# Sheet3.net
KiCad netlist of a schematic drawn in Altium Designer
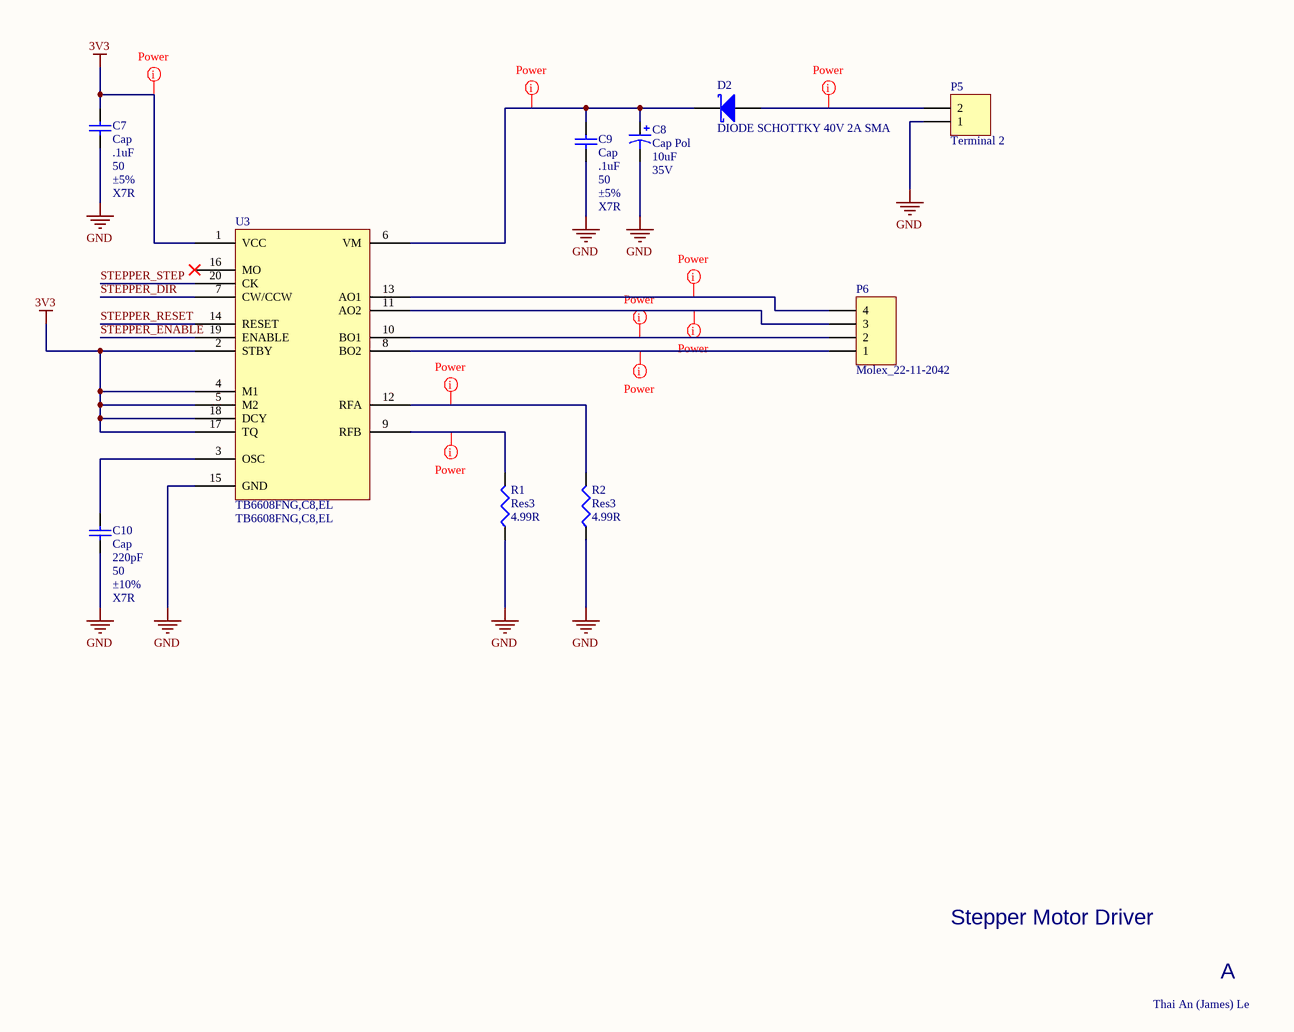
[diagram p0: Sheet3.SchDoc]

(export (version "E")
  (design (tool "Eeschema 10.0.6"))
  (components
    (comp (ref "C7")
      (value "Cap")
      (footprint "CAPC2012X09M")
      (description "CAP CER .1uF 50v X7R 0805")
      (fields
        (field (name "ALTIUM_VALUE") ".1uF")
        (field (name "WV") "50")
        (field (name "TOLERANCE") "±5%")
        (field (name "TYPE") "X7R")
        (field (name "MPN") "C0805C104J5RACTU")
      )
      (libsource (lib "esd_library") (part "CAP-X7R-.1uF-50V-±5%"))
    )
    (comp (ref "C8")
      (value "Cap Pol")
      (footprint "CAPACITOR_5MM")
      (description "CAP 85C 10uF ±20% 35V WX Series Aluminum Electrolytic")
      (fields
        (field (name "ALTIUM_VALUE") "10uF")
        (field (name "VOLTAGE") "35V")
        (field (name "MPN") "UWX1V100MCL1GB")
      )
      (libsource (lib "esd_library") (part "Cap Polar-10uF-35V"))
    )
    (comp (ref "C9")
      (value "Cap")
      (footprint "CAPC2012X09M")
      (description "CAP CER .1uF 50v X7R 0805")
      (fields
        (field (name "ALTIUM_VALUE") ".1uF")
        (field (name "WV") "50")
        (field (name "TOLERANCE") "±5%")
        (field (name "TYPE") "X7R")
        (field (name "MPN") "C0805C104J5RACTU")
      )
      (libsource (lib "esd_library") (part "CAP-X7R-.1uF-50V-±5%"))
    )
    (comp (ref "C10")
      (value "Cap")
      (footprint "CAPC2012X09M")
      (description "CAP CER 220pF 50v X7R 0805")
      (fields
        (field (name "ALTIUM_VALUE") "220pF")
        (field (name "WV") "50")
        (field (name "TOLERANCE") "±10%")
        (field (name "TYPE") "X7R")
        (field (name "MPN") "C0805C221K5RACTU")
      )
      (libsource (lib "esd_library") (part "CAP-X7R-220pF-50V-±10%"))
    )
    (comp (ref "D2")
      (value "DIODE SCHOTTKY 40V 2A SMA")
      (footprint "DIOM4326X23M")
      (description "Schottky Rectifier")
      (fields (field (name "MPN") "B240A-13-F"))
      (libsource (lib "esd_library") (part "DIODE SCHOTTKY 40V 2A SMA"))
    )
    (comp (ref "P5")
      (value "Terminal 2")
      (footprint "TYCO_282841_2")
      (description "Terminal, 2-Pin")
      (fields (field (name "MPN") "282841-2") (field (name "PUBLISHER") "Altium Limited"))
      (libsource (lib "esd_library") (part "Terminal 2"))
    )
    (comp (ref "P6")
      (value "Molex_22-11-2042")
      (footprint "MOLEX-22-11-2042")
      (description "CONN HEADER 4POS .100 VERT GOLD")
      (fields (field (name "MPN") "0022112042"))
      (libsource (lib "esd_library") (part "Molex_22-11-2042"))
    )
    (comp (ref "R1")
      (value "Res3")
      (footprint "RESC2112X05M")
      (description "RES SMD 4.99R OHM 1% 1/8W 0805")
      (fields (field (name "ALTIUM_VALUE") "4.99R") (field (name "MPN") "CRCW08054R99FKEA"))
      (libsource (lib "esd_library") (part "Resistor_4.99R"))
    )
    (comp (ref "R2")
      (value "Res3")
      (footprint "RESC2112X05M")
      (description "RES SMD 4.99R OHM 1% 1/8W 0805")
      (fields (field (name "ALTIUM_VALUE") "4.99R") (field (name "MPN") "CRCW08054R99FKEA"))
      (libsource (lib "esd_library") (part "Resistor_4.99R"))
    )
    (comp (ref "U3")
      (value "TB6608FNG,C8,EL")
      (footprint "TSOP65P640X160-20M")
      (description "IC MTR DRV BIPLR 2.7-5.5V 20SSOP")
      (fields (field (name "MPN") "TB6608FNG,C8,EL"))
      (libsource (lib "esd_library") (part "TB6608FNG,C8,EL"))
    )
  )
  (nets
    (net (code "1") (name "/STEPPER_DIR") (class "Default")
      (node (ref "U3") (pin "7") (pinfunction "CW/CCW_7") (pintype "passive"))
    )
    (net (code "2") (name "/STEPPER_ENABLE") (class "Default")
      (node (ref "U3") (pin "19") (pinfunction "ENABLE_19") (pintype "passive"))
    )
    (net (code "3") (name "/STEPPER_RESET") (class "Default")
      (node (ref "U3") (pin "14") (pinfunction "RESET_14") (pintype "passive"))
    )
    (net (code "4") (name "/STEPPER_STEP") (class "Default")
      (node (ref "U3") (pin "20") (pinfunction "CK_20") (pintype "passive"))
    )
    (net (code "5") (name "3V3") (class "Default")
      (node (ref "C7") (pin "2") (pinfunction "2_2") (pintype "passive"))
      (node (ref "U3") (pin "1") (pinfunction "VCC_1") (pintype "passive"))
      (node (ref "U3") (pin "17") (pinfunction "TQ_17") (pintype "passive"))
      (node (ref "U3") (pin "18") (pinfunction "DCY_18") (pintype "passive"))
      (node (ref "U3") (pin "2") (pinfunction "STBY_2") (pintype "passive"))
      (node (ref "U3") (pin "4") (pinfunction "M1_4") (pintype "passive"))
      (node (ref "U3") (pin "5") (pinfunction "M2_5") (pintype "passive"))
    )
    (net (code "6") (name "GND") (class "Default")
      (node (ref "C10") (pin "1") (pinfunction "1_1") (pintype "passive"))
      (node (ref "C7") (pin "1") (pinfunction "1_1") (pintype "passive"))
      (node (ref "C8") (pin "2") (pinfunction "2_2") (pintype "passive"))
      (node (ref "C9") (pin "1") (pinfunction "1_1") (pintype "passive"))
      (node (ref "P5") (pin "1") (pinfunction "1_1") (pintype "passive"))
      (node (ref "R1") (pin "1") (pinfunction "1_1") (pintype "passive"))
      (node (ref "R2") (pin "1") (pinfunction "1_1") (pintype "passive"))
      (node (ref "U3") (pin "15") (pinfunction "GND_15") (pintype "passive"))
    )
    (net (code "7") (name "Net-(D2-A)") (class "Default")
      (node (ref "D2") (pin "2") (pinfunction "A_2") (pintype "passive"))
      (node (ref "P5") (pin "2") (pinfunction "2_2") (pintype "passive"))
    )
    (net (code "8") (name "Net-(D2-K)") (class "Default")
      (node (ref "C8") (pin "1") (pinfunction "1_1") (pintype "passive"))
      (node (ref "C9") (pin "2") (pinfunction "2_2") (pintype "passive"))
      (node (ref "D2") (pin "1") (pinfunction "K_1") (pintype "passive"))
      (node (ref "U3") (pin "6") (pinfunction "VM_6") (pintype "passive"))
    )
    (net (code "9") (name "Net-(U3-AO1)") (class "Default")
      (node (ref "P6") (pin "4") (pinfunction "4_4") (pintype "passive"))
      (node (ref "U3") (pin "13") (pinfunction "AO1_13") (pintype "passive"))
    )
    (net (code "10") (name "Net-(U3-AO2)") (class "Default")
      (node (ref "P6") (pin "3") (pinfunction "3_3") (pintype "passive"))
      (node (ref "U3") (pin "11") (pinfunction "AO2_11") (pintype "passive"))
    )
    (net (code "11") (name "Net-(U3-BO1)") (class "Default")
      (node (ref "P6") (pin "2") (pinfunction "2_2") (pintype "passive"))
      (node (ref "U3") (pin "10") (pinfunction "BO1_10") (pintype "passive"))
    )
    (net (code "12") (name "Net-(U3-BO2)") (class "Default")
      (node (ref "P6") (pin "1") (pinfunction "1_1") (pintype "passive"))
      (node (ref "U3") (pin "8") (pinfunction "BO2_8") (pintype "passive"))
    )
    (net (code "13") (name "Net-(U3-OSC)") (class "Default")
      (node (ref "C10") (pin "2") (pinfunction "2_2") (pintype "passive"))
      (node (ref "U3") (pin "3") (pinfunction "OSC_3") (pintype "passive"))
    )
    (net (code "14") (name "Net-(U3-RFA)") (class "Default")
      (node (ref "R2") (pin "2") (pinfunction "2_2") (pintype "passive"))
      (node (ref "U3") (pin "12") (pinfunction "RFA_12") (pintype "passive"))
    )
    (net (code "15") (name "Net-(U3-RFB)") (class "Default")
      (node (ref "R1") (pin "2") (pinfunction "2_2") (pintype "passive"))
      (node (ref "U3") (pin "9") (pinfunction "RFB_9") (pintype "passive"))
    )
    (net (code "16") (name "unconnected-(U3-MO-Pad16)") (class "Default")
      (node (ref "U3") (pin "16") (pinfunction "MO_16") (pintype "passive+no_connect"))
    )
  )
)
